# carlight_schematic.net
KiCad netlist of a schematic drawn in EAGLE
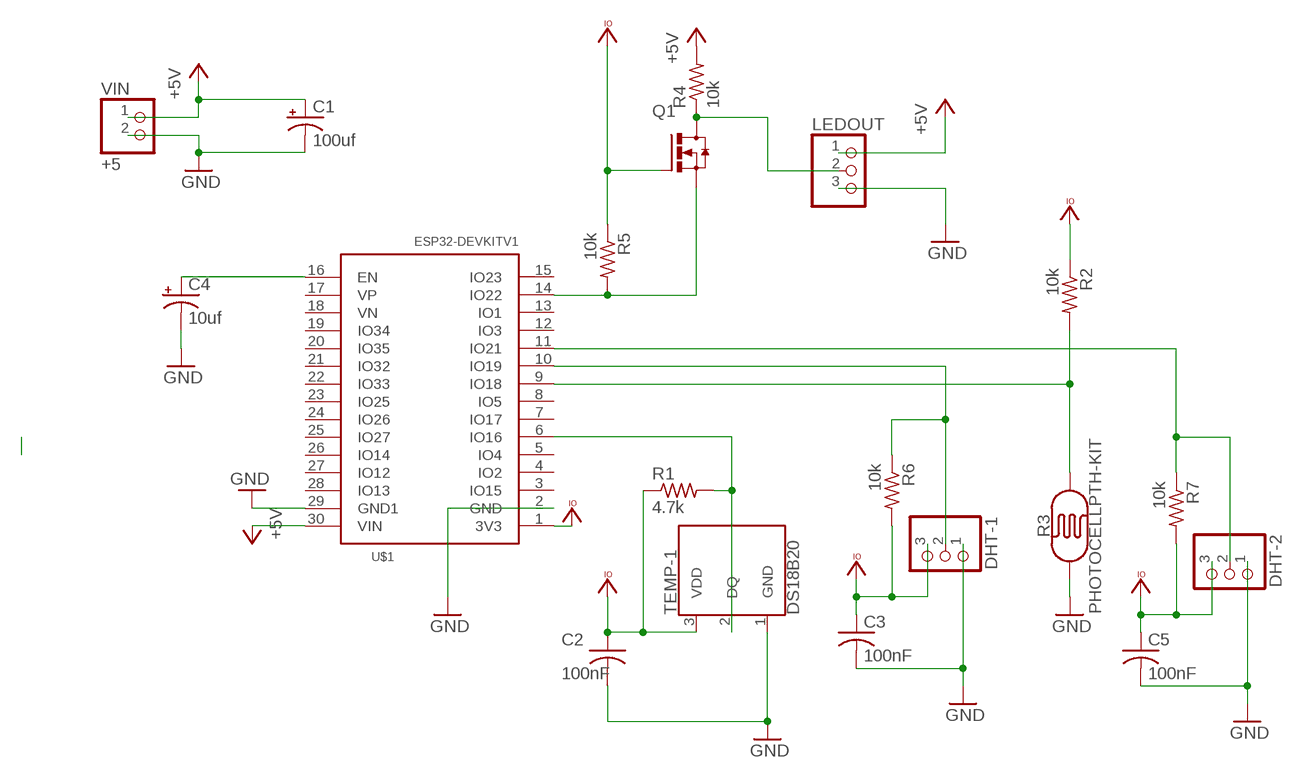
[diagram p0: schematic, sheet 1]

(export (version "E")
  (design (tool "Eeschema 10.0.6"))
  (components
    (comp (ref "C1")
      (value "100uf")
      (footprint "eagle-import:153CLV-0605")
      (libsource (lib "eagle-import") (part "CPOL-US153CLV-0605"))
    )
    (comp (ref "C2")
      (value "100nF")
      (footprint "eagle-import:C0805")
      (libsource (lib "eagle-import") (part "C-USC0805"))
    )
    (comp (ref "C3")
      (value "100nF")
      (footprint "eagle-import:C0805")
      (libsource (lib "eagle-import") (part "C-USC0805"))
    )
    (comp (ref "C4")
      (value "10uf")
      (footprint "eagle-import:153CLV-0605")
      (libsource (lib "eagle-import") (part "CPOL-US153CLV-0605"))
    )
    (comp (ref "C5")
      (value "100nF")
      (footprint "eagle-import:C0805")
      (libsource (lib "eagle-import") (part "C-USC0805"))
    )
    (comp (ref "DHT-1")
      (value "PINHD-1X3")
      (footprint "eagle-import:1X03")
      (libsource (lib "eagle-import") (part "PINHD-1X3"))
    )
    (comp (ref "DHT-2")
      (value "PINHD-1X3")
      (footprint "eagle-import:1X03")
      (libsource (lib "eagle-import") (part "PINHD-1X3"))
    )
    (comp (ref "LEDOUT")
      (value "PINHD-1X3")
      (footprint "eagle-import:1X03")
      (libsource (lib "eagle-import") (part "PINHD-1X3"))
    )
    (comp (ref "Q1")
      (value "2N7002")
      (footprint "eagle-import:SOT23-3")
      (fields
        (field (name "DIGIKEY_PART_NUMBER") "1727-2764-1-ND")
        (field (name "MANUFACTURER") "Nexperia USA Inc.")
        (field (name "MPN") "2N7002,215")
        (field (name "CREATED_BY") "PCBLayout.com")
      )
      (libsource (lib "eagle-import") (part "2N7002,215"))
    )
    (comp (ref "R1")
      (value "4.7k")
      (footprint "eagle-import:R0805")
      (libsource (lib "eagle-import") (part "resistor_348_R-US_R0805"))
    )
    (comp (ref "R2")
      (value "10k")
      (footprint "eagle-import:R0805")
      (libsource (lib "eagle-import") (part "resistor_348_R-US_R0805"))
    )
    (comp (ref "R3")
      (value "PHOTOCELLPTH-KIT")
      (footprint "eagle-import:PHOTOCELL-KIT")
      (libsource (lib "eagle-import") (part "PHOTOCELLPTH-KIT"))
    )
    (comp (ref "R4")
      (value "10k")
      (footprint "eagle-import:R0805")
      (libsource (lib "eagle-import") (part "R-US_R0805"))
    )
    (comp (ref "R5")
      (value "10k")
      (footprint "eagle-import:R0805")
      (libsource (lib "eagle-import") (part "R-US_R0805"))
    )
    (comp (ref "R6")
      (value "10k")
      (footprint "eagle-import:R0805")
      (libsource (lib "eagle-import") (part "R-US_R0805"))
    )
    (comp (ref "R7")
      (value "10k")
      (footprint "eagle-import:R0805")
      (libsource (lib "eagle-import") (part "R-US_R0805"))
    )
    (comp (ref "TEMP-1")
      (value "DS18B20")
      (footprint "eagle-import:TO-92-AMMO")
      (libsource (lib "eagle-import") (part "DS18B20"))
    )
    (comp (ref "U$1")
      (value "ESP32DEVKITV1")
      (footprint "eagle-import:ESP32-DEVKITV1")
      (libsource (lib "eagle-import") (part "ESP32DEVKITV1"))
    )
    (comp (ref "VIN")
      (value "+5")
      (footprint "eagle-import:1X02")
      (libsource (lib "eagle-import") (part "PINHD-1X2"))
    )
  )
  (nets
    (net (code "1") (name "+5V") (class "Default")
      (node (ref "C1") (pin "+") (pinfunction "+_+") (pintype "passive"))
      (node (ref "LEDOUT") (pin "1") (pinfunction "1_1") (pintype "passive"))
      (node (ref "R4") (pin "2") (pinfunction "2_2") (pintype "passive"))
      (node (ref "U$1") (pin "30") (pinfunction "VIN_30") (pintype "bidirectional"))
      (node (ref "VIN") (pin "1") (pinfunction "1_1") (pintype "passive"))
    )
    (net (code "2") (name "GND") (class "Default")
      (node (ref "C1") (pin "-") (pinfunction "-_-") (pintype "passive"))
      (node (ref "C2") (pin "2") (pinfunction "2_2") (pintype "passive"))
      (node (ref "C3") (pin "2") (pinfunction "2_2") (pintype "passive"))
      (node (ref "C4") (pin "-") (pinfunction "-_-") (pintype "passive"))
      (node (ref "C5") (pin "2") (pinfunction "2_2") (pintype "passive"))
      (node (ref "DHT-1") (pin "1") (pinfunction "1_1") (pintype "passive"))
      (node (ref "DHT-2") (pin "1") (pinfunction "1_1") (pintype "passive"))
      (node (ref "LEDOUT") (pin "3") (pinfunction "3_3") (pintype "passive"))
      (node (ref "R3") (pin "1") (pinfunction "P$1_1") (pintype "bidirectional"))
      (node (ref "TEMP-1") (pin "1") (pinfunction "GND_1") (pintype "power_in"))
      (node (ref "U$1") (pin "2") (pinfunction "GND_2") (pintype "bidirectional"))
      (node (ref "U$1") (pin "29") (pinfunction "GND1_29") (pintype "bidirectional"))
      (node (ref "VIN") (pin "2") (pinfunction "2_2") (pintype "passive"))
    )
    (net (code "3") (name "Net-(Q1-D)") (class "Default")
      (node (ref "LEDOUT") (pin "2") (pinfunction "2_2") (pintype "passive"))
      (node (ref "Q1") (pin "3") (pinfunction "D_3") (pintype "passive"))
      (node (ref "R4") (pin "1") (pinfunction "1_1") (pintype "passive"))
    )
    (net (code "4") (name "Net-(Q1-S)") (class "Default")
      (node (ref "Q1") (pin "2") (pinfunction "S_2") (pintype "passive"))
      (node (ref "R5") (pin "2") (pinfunction "2_2") (pintype "passive"))
      (node (ref "U$1") (pin "14") (pinfunction "IO22_14") (pintype "bidirectional"))
    )
    (net (code "5") (name "Net-(R3-P$2)") (class "Default")
      (node (ref "R2") (pin "2") (pinfunction "2_2") (pintype "passive"))
      (node (ref "R3") (pin "2") (pinfunction "P$2_2") (pintype "bidirectional"))
      (node (ref "U$1") (pin "9") (pinfunction "IO18_9") (pintype "bidirectional"))
    )
    (net (code "6") (name "Net-(TEMP-1-DQ)") (class "Default")
      (node (ref "R1") (pin "2") (pinfunction "2_2") (pintype "passive"))
      (node (ref "TEMP-1") (pin "2") (pinfunction "DQ_2") (pintype "bidirectional"))
      (node (ref "U$1") (pin "6") (pinfunction "IO16_6") (pintype "bidirectional"))
    )
    (net (code "7") (name "Net-(U$1-EN)") (class "Default")
      (node (ref "C4") (pin "+") (pinfunction "+_+") (pintype "passive"))
      (node (ref "U$1") (pin "16") (pinfunction "EN_16") (pintype "bidirectional"))
    )
    (net (code "8") (name "Net-(U$1-IO19)") (class "Default")
      (node (ref "DHT-1") (pin "2") (pinfunction "2_2") (pintype "passive"))
      (node (ref "R6") (pin "1") (pinfunction "1_1") (pintype "passive"))
      (node (ref "U$1") (pin "10") (pinfunction "IO19_10") (pintype "bidirectional"))
    )
    (net (code "9") (name "Net-(U$1-IO21)") (class "Default")
      (node (ref "DHT-2") (pin "2") (pinfunction "2_2") (pintype "passive"))
      (node (ref "R7") (pin "1") (pinfunction "1_1") (pintype "passive"))
      (node (ref "U$1") (pin "11") (pinfunction "IO21_11") (pintype "bidirectional"))
    )
    (net (code "10") (name "VCCIO") (class "Default")
      (node (ref "C2") (pin "1") (pinfunction "1_1") (pintype "passive"))
      (node (ref "C3") (pin "1") (pinfunction "1_1") (pintype "passive"))
      (node (ref "C5") (pin "1") (pinfunction "1_1") (pintype "passive"))
      (node (ref "DHT-1") (pin "3") (pinfunction "3_3") (pintype "passive"))
      (node (ref "DHT-2") (pin "3") (pinfunction "3_3") (pintype "passive"))
      (node (ref "Q1") (pin "1") (pinfunction "G_1") (pintype "passive"))
      (node (ref "R1") (pin "1") (pinfunction "1_1") (pintype "passive"))
      (node (ref "R2") (pin "1") (pinfunction "1_1") (pintype "passive"))
      (node (ref "R5") (pin "1") (pinfunction "1_1") (pintype "passive"))
      (node (ref "R6") (pin "2") (pinfunction "2_2") (pintype "passive"))
      (node (ref "R7") (pin "2") (pinfunction "2_2") (pintype "passive"))
      (node (ref "TEMP-1") (pin "3") (pinfunction "VDD_3") (pintype "power_in"))
      (node (ref "U$1") (pin "1") (pinfunction "3V3_1") (pintype "bidirectional"))
    )
    (net (code "11") (name "unconnected-(U$1-IO1-Pad13)") (class "Default")
      (node (ref "U$1") (pin "13") (pinfunction "IO1_13") (pintype "bidirectional"))
    )
    (net (code "12") (name "unconnected-(U$1-IO2-Pad4)") (class "Default")
      (node (ref "U$1") (pin "4") (pinfunction "IO2_4") (pintype "bidirectional"))
    )
    (net (code "13") (name "unconnected-(U$1-IO3-Pad12)") (class "Default")
      (node (ref "U$1") (pin "12") (pinfunction "IO3_12") (pintype "bidirectional"))
    )
    (net (code "14") (name "unconnected-(U$1-IO4-Pad5)") (class "Default")
      (node (ref "U$1") (pin "5") (pinfunction "IO4_5") (pintype "bidirectional"))
    )
    (net (code "15") (name "unconnected-(U$1-IO5-Pad8)") (class "Default")
      (node (ref "U$1") (pin "8") (pinfunction "IO5_8") (pintype "bidirectional"))
    )
    (net (code "16") (name "unconnected-(U$1-IO12-Pad27)") (class "Default")
      (node (ref "U$1") (pin "27") (pinfunction "IO12_27") (pintype "bidirectional"))
    )
    (net (code "17") (name "unconnected-(U$1-IO13-Pad28)") (class "Default")
      (node (ref "U$1") (pin "28") (pinfunction "IO13_28") (pintype "bidirectional"))
    )
    (net (code "18") (name "unconnected-(U$1-IO14-Pad26)") (class "Default")
      (node (ref "U$1") (pin "26") (pinfunction "IO14_26") (pintype "bidirectional"))
    )
    (net (code "19") (name "unconnected-(U$1-IO15-Pad3)") (class "Default")
      (node (ref "U$1") (pin "3") (pinfunction "IO15_3") (pintype "bidirectional"))
    )
    (net (code "20") (name "unconnected-(U$1-IO17-Pad7)") (class "Default")
      (node (ref "U$1") (pin "7") (pinfunction "IO17_7") (pintype "bidirectional"))
    )
    (net (code "21") (name "unconnected-(U$1-IO23-Pad15)") (class "Default")
      (node (ref "U$1") (pin "15") (pinfunction "IO23_15") (pintype "bidirectional"))
    )
    (net (code "22") (name "unconnected-(U$1-IO25-Pad23)") (class "Default")
      (node (ref "U$1") (pin "23") (pinfunction "IO25_23") (pintype "bidirectional"))
    )
    (net (code "23") (name "unconnected-(U$1-IO26-Pad24)") (class "Default")
      (node (ref "U$1") (pin "24") (pinfunction "IO26_24") (pintype "bidirectional"))
    )
    (net (code "24") (name "unconnected-(U$1-IO27-Pad25)") (class "Default")
      (node (ref "U$1") (pin "25") (pinfunction "IO27_25") (pintype "bidirectional"))
    )
    (net (code "25") (name "unconnected-(U$1-IO32-Pad21)") (class "Default")
      (node (ref "U$1") (pin "21") (pinfunction "IO32_21") (pintype "bidirectional"))
    )
    (net (code "26") (name "unconnected-(U$1-IO33-Pad22)") (class "Default")
      (node (ref "U$1") (pin "22") (pinfunction "IO33_22") (pintype "bidirectional"))
    )
    (net (code "27") (name "unconnected-(U$1-IO34-Pad19)") (class "Default")
      (node (ref "U$1") (pin "19") (pinfunction "IO34_19") (pintype "bidirectional"))
    )
    (net (code "28") (name "unconnected-(U$1-IO35-Pad20)") (class "Default")
      (node (ref "U$1") (pin "20") (pinfunction "IO35_20") (pintype "bidirectional"))
    )
    (net (code "29") (name "unconnected-(U$1-VN-Pad18)") (class "Default")
      (node (ref "U$1") (pin "18") (pinfunction "VN_18") (pintype "bidirectional"))
    )
    (net (code "30") (name "unconnected-(U$1-VP-Pad17)") (class "Default")
      (node (ref "U$1") (pin "17") (pinfunction "VP_17") (pintype "bidirectional"))
    )
  )
)
